# POE-3V3-boardschem.net
KiCad netlist of a schematic drawn in Altium Designer
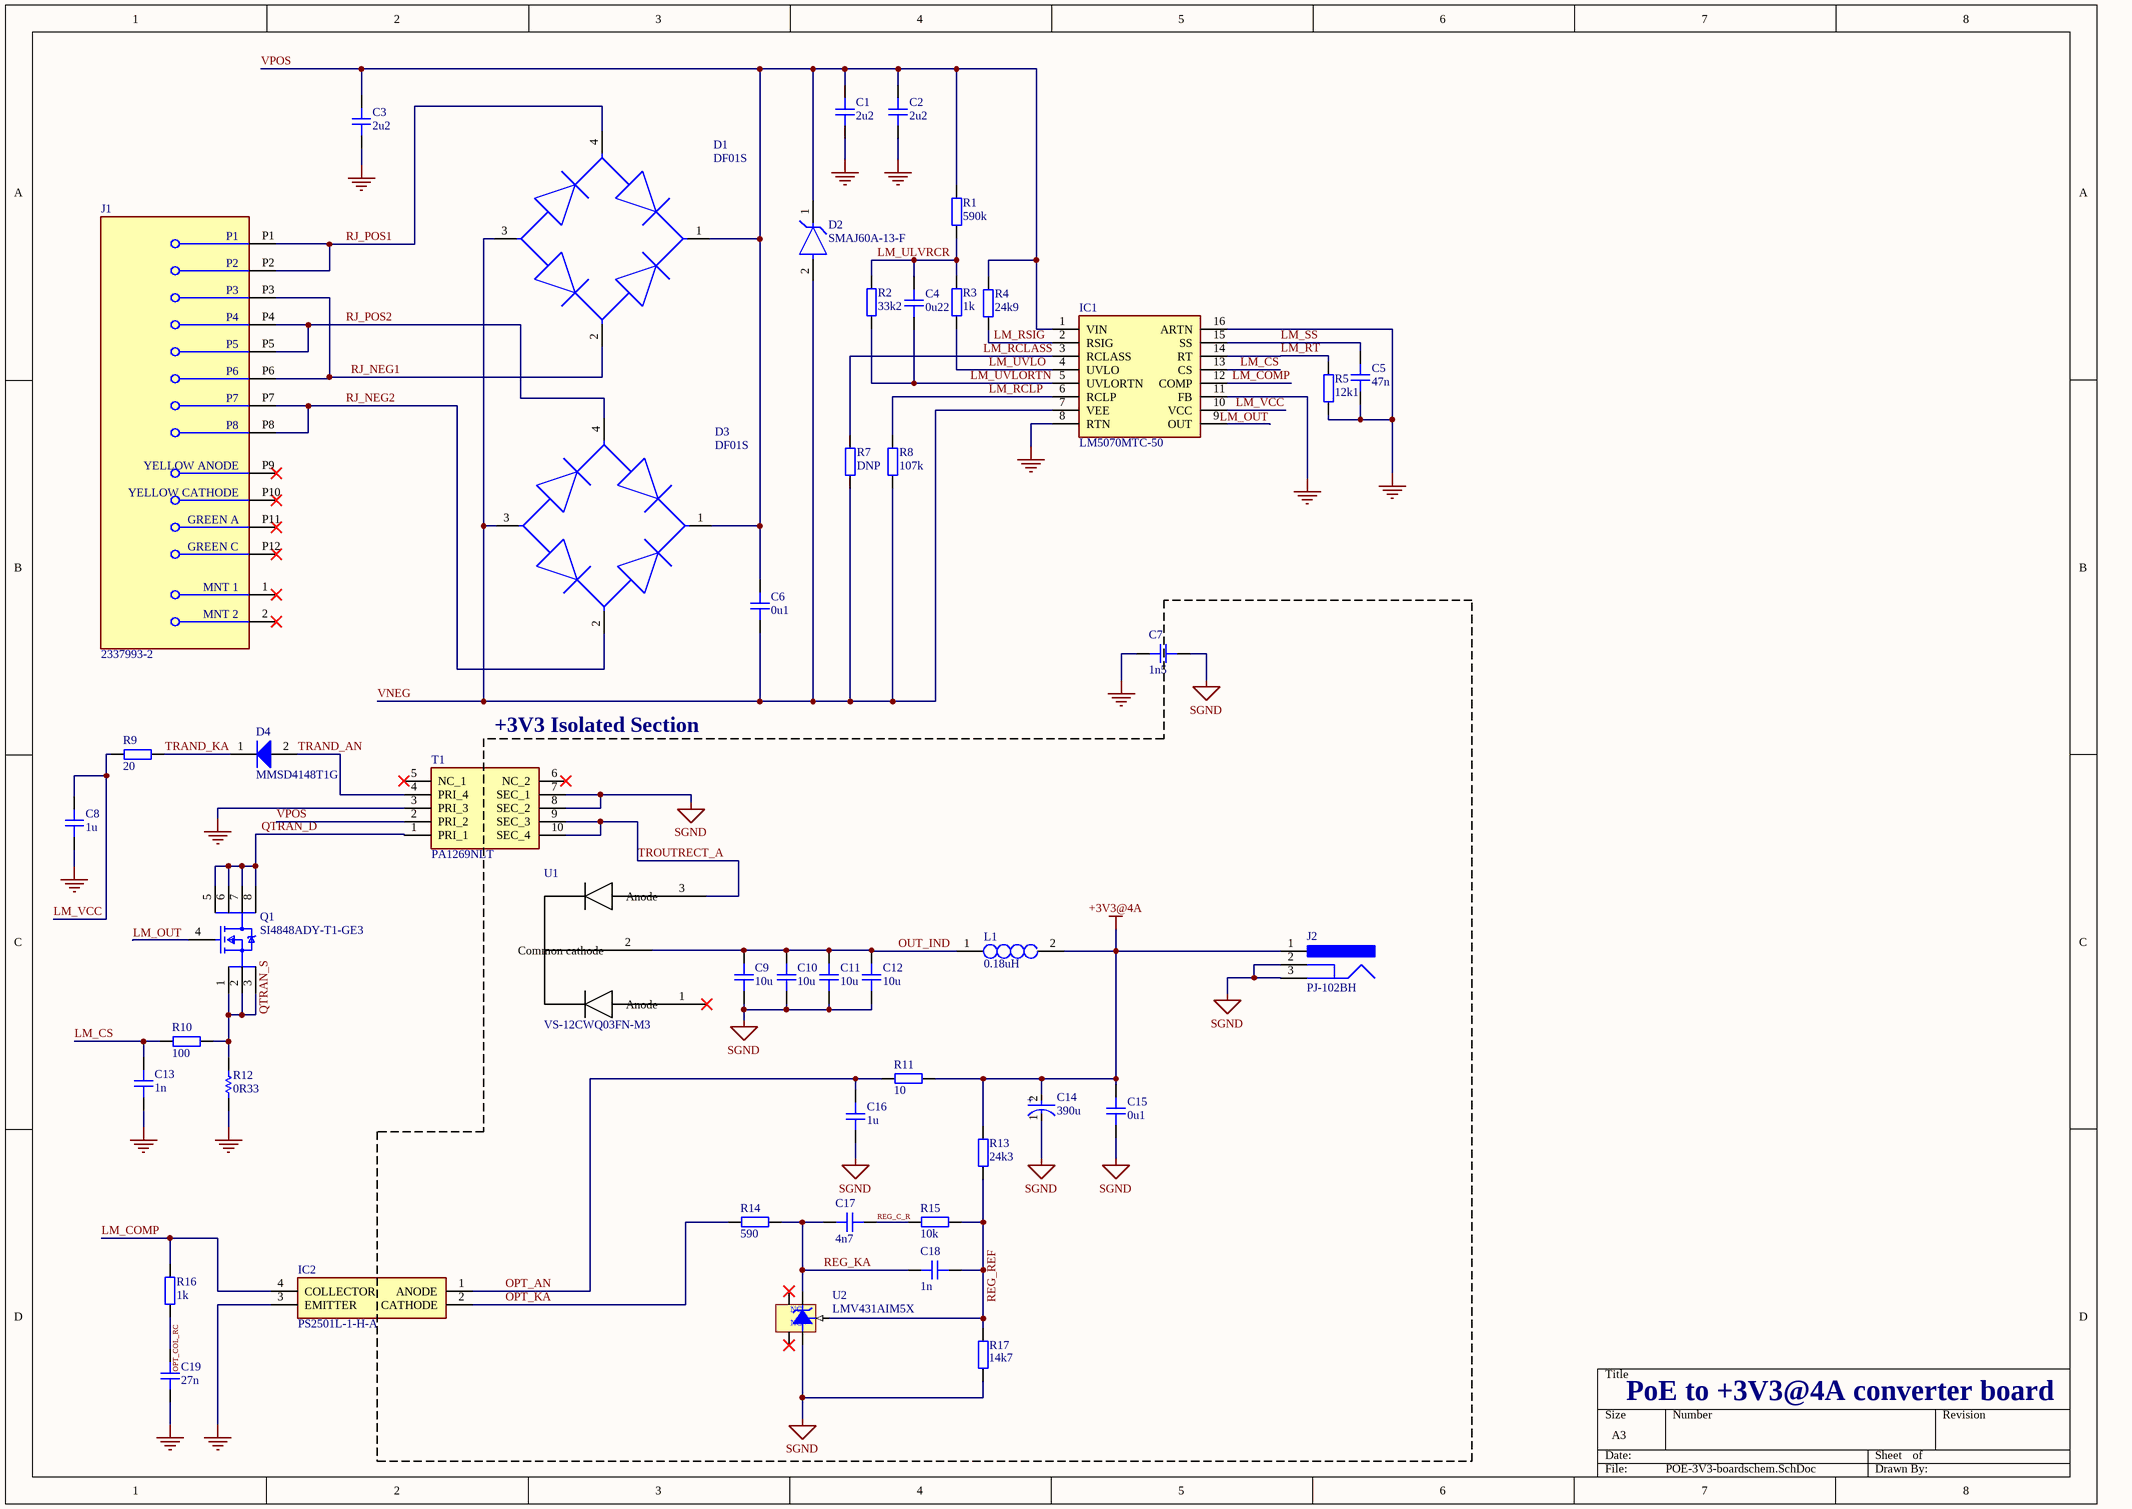
[diagram p0: POE-3V3-boardschem.SchDoc]

(export (version "E")
  (design (tool "Eeschema 10.0.6"))
  (components
    (comp (ref "C1")
      (value "2u2")
      (footprint "CAP_0805")
      (description "Capacitor SMD 0805")
      (libsource (lib "Schematic-Lib-PhilsLab") (part "CAP_0805"))
    )
    (comp (ref "C2")
      (value "2u2")
      (footprint "CAP_0805")
      (description "Capacitor SMD 0805")
      (libsource (lib "Schematic-Lib-PhilsLab") (part "CAP_0805"))
    )
    (comp (ref "C3")
      (value "2u2")
      (footprint "CAP_0805")
      (description "Capacitor SMD 0805")
      (libsource (lib "Schematic-Lib-PhilsLab") (part "CAP_0805"))
    )
    (comp (ref "C4")
      (value "0u22")
      (footprint "CAP_0805")
      (description "Capacitor SMD 0805")
      (libsource (lib "Schematic-Lib-PhilsLab") (part "CAP_0805"))
    )
    (comp (ref "C5")
      (value "47n")
      (footprint "CAP_0805")
      (description "Capacitor SMD 0805")
      (libsource (lib "Schematic-Lib-PhilsLab") (part "CAP_0805"))
    )
    (comp (ref "C6")
      (value "0u1")
      (footprint "CAP_0805")
      (description "Capacitor SMD 0805")
      (libsource (lib "Schematic-Lib-PhilsLab") (part "CAP_0805"))
    )
    (comp (ref "C7")
      (value "1n5")
      (footprint "CAP_0805")
      (description "Capacitor SMD 0805")
      (libsource (lib "Schematic-Lib-PhilsLab") (part "CAP_0805"))
    )
    (comp (ref "C8")
      (value "1u")
      (footprint "CAP_0805")
      (description "Capacitor SMD 0805")
      (libsource (lib "Schematic-Lib-PhilsLab") (part "CAP_0805"))
    )
    (comp (ref "C9")
      (value "10u")
      (footprint "CAP_1206")
      (description "Capacitor SMD 1206")
      (libsource (lib "Schematic-Lib-PhilsLab") (part "CAP_1206"))
    )
    (comp (ref "C10")
      (value "10u")
      (footprint "CAP_1206")
      (description "Capacitor SMD 1206")
      (libsource (lib "Schematic-Lib-PhilsLab") (part "CAP_1206"))
    )
    (comp (ref "C11")
      (value "10u")
      (footprint "CAP_1206")
      (description "Capacitor SMD 1206")
      (libsource (lib "Schematic-Lib-PhilsLab") (part "CAP_1206"))
    )
    (comp (ref "C12")
      (value "10u")
      (footprint "CAP_1206")
      (description "Capacitor SMD 1206")
      (libsource (lib "Schematic-Lib-PhilsLab") (part "CAP_1206"))
    )
    (comp (ref "C13")
      (value "1n")
      (footprint "CAP_0805")
      (description "Capacitor SMD 0805")
      (libsource (lib "Schematic-Lib-PhilsLab") (part "CAP_0805"))
    )
    (comp (ref "C14")
      (value "390u")
      (footprint "FP-RAD-TH-D_8_0_5-L_15_1-MFG")
      (description "Aluminum Electrolytic Capacitors (Radial Lead Type) 390uF ±20% 25V")
      (fields (field (name "TOLERANCE") "20%") (field (name "VOLTAGE") "25V"))
      (libsource (lib "Altium Content Vault") (part "a00bbbee19879c290e62620ae7e47b1"))
    )
    (comp (ref "C15")
      (value "0u1")
      (footprint "CAP_0805")
      (description "Capacitor SMD 0805")
      (libsource (lib "Schematic-Lib-PhilsLab") (part "CAP_0805"))
    )
    (comp (ref "C16")
      (value "1u")
      (footprint "CAP_1206")
      (description "Capacitor SMD 1206")
      (libsource (lib "Schematic-Lib-PhilsLab") (part "CAP_1206"))
    )
    (comp (ref "C17")
      (value "4n7")
      (footprint "CAP_1206")
      (description "Capacitor SMD 1206")
      (libsource (lib "Schematic-Lib-PhilsLab") (part "CAP_1206"))
    )
    (comp (ref "C18")
      (value "1n")
      (footprint "CAP_1206")
      (description "Capacitor SMD 1206")
      (libsource (lib "Schematic-Lib-PhilsLab") (part "CAP_1206"))
    )
    (comp (ref "C19")
      (value "27n")
      (footprint "CAP_1206")
      (description "Capacitor SMD 1206")
      (libsource (lib "Schematic-Lib-PhilsLab") (part "CAP_1206"))
    )
    (comp (ref "D1")
      (value "DF01S")
      (footprint "FP-DF-S-MFG")
      (description "BRIDGE RECT 1PHASE 100V 1A DFS")
      (libsource (lib "Altium Content Vault") (part "07528f16604ad27f2258f3ec450d36f"))
    )
    (comp (ref "D2")
      (value "SMAJ60A-13-F")
      (footprint "FP-SMA-MFG")
      (description "TVS DIODE 60V 96.8V SMA")
      (fields
        (field (name "MANUFACTURER") "Diodes Inc.")
        (field (name "OCTOPART") "https://octopart.com/smaj60a-13-f-diodes+inc.-350240")
      )
      (libsource (lib "Altium Content Vault") (part "f813f71cba58e380607f5dd3caf9714"))
    )
    (comp (ref "D3")
      (value "DF01S")
      (footprint "FP-DF-S-MFG")
      (description "BRIDGE RECT 1PHASE 100V 1A DFS")
      (libsource (lib "Altium Content Vault") (part "07528f16604ad27f2258f3ec450d36f"))
    )
    (comp (ref "D4")
      (value "MMSD4148T1G")
      (footprint "ONSC-SOD-123-2-425-04_V")
      (description "Switching Diode, 2-Pin SOD-123, Pb-Free, Tape and Reel")
      (fields (field (name "MANUFACTURER") "On Semiconductor"))
      (libsource (lib "Altium Content Vault") (part "ONSC-D-K1A2-2"))
    )
    (comp (ref "IC1")
      (value "LM5070MTC-50")
      (footprint "SamacSys:SOP65P640X120-16N")
      (description "Integrated Circuit")
      (fields (field (name "MOUSER PART NUMBER") "926-LM5070MTC-50"))
      (libsource (lib "*") (part "LM5070MTC-50"))
    )
    (comp (ref "IC2")
      (value "PS2501L-1-H-A")
      (footprint "SamacSys:SOP254P960X400-4N")
      (description "Integrated Circuit")
      (fields (field (name "MOUSER PART NUMBER") "968-PS2501L-1-H-A"))
      (libsource (lib "*") (part "PS2501L-1-H-A"))
    )
    (comp (ref "J1")
      (value "2337993-2")
      (footprint "FP-2337993-2-MFG")
      (description "RJ45 JACK MAG. POE 10/100 LED 1X")
      (fields
        (field (name "MANUFACTURER") "TE Connectivity")
        (field (name "OCTOPART") "https://octopart.com/2337993-2-te+connectivity-99778114")
      )
      (libsource (lib "Altium Content Vault") (part "b4e1c9a47ad5bbbc9e514b05e68767f"))
    )
    (comp (ref "J2")
      (value "PJ-102BH")
      (footprint "CUI-PJ-102BH_V")
      (fields (field (name "MANUFACTURER") "CUIInc."))
      (libsource (lib "Altium Content Vault") (part "JACK-2CD3-RN"))
    )
    (comp (ref "L1")
      (value "0.18uH")
      (footprint "SamacSys:DO1813H181MLD")
      (description "Inductor")
      (fields
        (field (name "MANUFACTURER_PART_NUMBER") "DO1813H-181MLD")
        (field (name "MOUSER PART NUMBER") "994-DO1813H-181MLD")
      )
      (libsource (lib "*") (part "DO1813H-181MLD"))
    )
    (comp (ref "Q1")
      (value "SI4848ADY-T1-GE3")
      (footprint "FP-C-06527-MFG")
      (description "MOSFET N-CH 150V 5.5A 8SOIC")
      (fields
        (field (name "MANUFACTURER") "Vishay")
        (field (name "OCTOPART") "https://octopart.com/si4848ady-t1-ge3-vishay-88182557")
      )
      (libsource (lib "Altium Content Vault") (part "7a16ee1d7ae3acce42eca13e4b0f561"))
    )
    (comp (ref "R1")
      (value "590k")
      (footprint "RES_0805")
      (description "Resistor SMD 0805")
      (libsource (lib "Schematic-Lib-PhilsLab") (part "RES_0805"))
    )
    (comp (ref "R2")
      (value "33k2")
      (footprint "RES_0805")
      (description "Resistor SMD 0805")
      (libsource (lib "Schematic-Lib-PhilsLab") (part "RES_0805"))
    )
    (comp (ref "R3")
      (value "1k")
      (footprint "RES_0805")
      (description "Resistor SMD 0805")
      (libsource (lib "Schematic-Lib-PhilsLab") (part "RES_0805"))
    )
    (comp (ref "R4")
      (value "24k9")
      (footprint "RES_0805")
      (description "Resistor SMD 0805")
      (libsource (lib "Schematic-Lib-PhilsLab") (part "RES_0805"))
    )
    (comp (ref "R5")
      (value "12k1")
      (footprint "RES_0805")
      (description "Resistor SMD 0805")
      (libsource (lib "Schematic-Lib-PhilsLab") (part "RES_0805"))
    )
    (comp (ref "R7")
      (value "DNP")
      (footprint "RES_0805")
      (description "Resistor SMD 0805")
      (libsource (lib "Schematic-Lib-PhilsLab") (part "RES_0805"))
    )
    (comp (ref "R8")
      (value "107k")
      (footprint "RES_0805")
      (description "Resistor SMD 0805")
      (libsource (lib "Schematic-Lib-PhilsLab") (part "RES_0805"))
    )
    (comp (ref "R9")
      (value "20")
      (footprint "RES_0805")
      (description "Resistor SMD 0805")
      (libsource (lib "Schematic-Lib-PhilsLab") (part "RES_0805"))
    )
    (comp (ref "R10")
      (value "100")
      (footprint "RES_0805")
      (description "Resistor SMD 0805")
      (libsource (lib "Schematic-Lib-PhilsLab") (part "RES_0805"))
    )
    (comp (ref "R11")
      (value "10")
      (footprint "RES_0805")
      (description "Resistor SMD 0805")
      (libsource (lib "Schematic-Lib-PhilsLab") (part "RES_0805"))
    )
    (comp (ref "R12")
      (value "0R33")
      (footprint "RESC3126X65X50NL10T20")
      (fields (field (name "PART NUMBER") "RL1210FR-070R33L") (field (name "MANUFACTURER") "Yageo"))
      (libsource (lib "Altium Content Vault") (part "RES"))
    )
    (comp (ref "R13")
      (value "24k3")
      (footprint "RES_0805")
      (description "Resistor SMD 0805")
      (libsource (lib "Schematic-Lib-PhilsLab") (part "RES_0805"))
    )
    (comp (ref "R14")
      (value "590")
      (footprint "RES_0805")
      (description "Resistor SMD 0805")
      (libsource (lib "Schematic-Lib-PhilsLab") (part "RES_0805"))
    )
    (comp (ref "R15")
      (value "10k")
      (footprint "RES_0805")
      (description "Resistor SMD 0805")
      (libsource (lib "Schematic-Lib-PhilsLab") (part "RES_0805"))
    )
    (comp (ref "R16")
      (value "1k")
      (footprint "RES_0805")
      (description "Resistor SMD 0805")
      (libsource (lib "Schematic-Lib-PhilsLab") (part "RES_0805"))
    )
    (comp (ref "R17")
      (value "14k7")
      (footprint "RES_0805")
      (description "Resistor SMD 0805")
      (libsource (lib "Schematic-Lib-PhilsLab") (part "RES_0805"))
    )
    (comp (ref "T1")
      (value "PA1269NLT")
      (footprint "SamacSys:PA1269NLT")
      (description "Transformer")
      (fields (field (name "MOUSER PART NUMBER") "673-PA1269NLT"))
      (libsource (lib "*") (part "PA1269NLT"))
    )
    (comp (ref "U1")
      (value "VS-12CWQ03FN-M3")
      (footprint "DPAK_03FN-M3_VIS")
      (description "Schottky - D-PAK")
      (fields (field (name "COPYRIGHT") "Copyright (C) 2025 Ultra Librarian. All rights reserved."))
      (libsource (lib "VS-12CWQ03FN-M3") (part "VS-12CWQ03FN-M3"))
    )
    (comp (ref "U2")
      (value "LMV431AIM5X")
      (footprint "DBV0005A_M")
      (description "Low-Voltage (1.24V) Adjustable Precision Shunt Regulators, 5-pin SOT-23")
      (fields (field (name "MANUFACTURER") "Texas Instruments"))
      (libsource (lib "Altium Content Vault") (part "PM-REG-LMV431-5"))
    )
  )
  (nets
    (net (code "1") (name "+3V3@4A") (class "Default")
      (node (ref "C14") (pin "2") (pinfunction "A_2") (pintype "passive"))
      (node (ref "C15") (pin "2") (pinfunction "2_2") (pintype "passive"))
      (node (ref "J2") (pin "1") (pinfunction "1_1") (pintype "passive"))
      (node (ref "L1") (pin "2") (pinfunction "2_2") (pintype "passive"))
      (node (ref "R11") (pin "2") (pinfunction "2_2") (pintype "passive"))
      (node (ref "R13") (pin "1") (pinfunction "1_1") (pintype "passive"))
    )
    (net (code "2") (name "/LM_COMP") (class "Default")
      (node (ref "IC1") (pin "12") (pinfunction "COMP_12") (pintype "passive"))
      (node (ref "IC2") (pin "4") (pinfunction "COLLECTOR_4") (pintype "passive"))
      (node (ref "R16") (pin "1") (pinfunction "1_1") (pintype "passive"))
    )
    (net (code "3") (name "/LM_CS") (class "Default")
      (node (ref "C13") (pin "2") (pinfunction "2_2") (pintype "passive"))
      (node (ref "IC1") (pin "13") (pinfunction "CS_13") (pintype "passive"))
      (node (ref "R10") (pin "2") (pinfunction "2_2") (pintype "passive"))
    )
    (net (code "4") (name "/LM_OUT") (class "Default")
      (node (ref "IC1") (pin "9") (pinfunction "OUT_9") (pintype "passive"))
      (node (ref "Q1") (pin "4") (pinfunction "G_4") (pintype "passive"))
    )
    (net (code "5") (name "/LM_RCLASS") (class "Default")
      (node (ref "IC1") (pin "3") (pinfunction "RCLASS_3") (pintype "passive"))
      (node (ref "R7") (pin "2") (pinfunction "2_2") (pintype "passive"))
    )
    (net (code "6") (name "/LM_RCLP") (class "Default")
      (node (ref "IC1") (pin "6") (pinfunction "RCLP_6") (pintype "passive"))
      (node (ref "R8") (pin "2") (pinfunction "2_2") (pintype "passive"))
    )
    (net (code "7") (name "/LM_RSIG") (class "Default")
      (node (ref "IC1") (pin "2") (pinfunction "RSIG_2") (pintype "passive"))
      (node (ref "R4") (pin "1") (pinfunction "1_1") (pintype "passive"))
    )
    (net (code "8") (name "/LM_RT") (class "Default")
      (node (ref "IC1") (pin "14") (pinfunction "RT_14") (pintype "passive"))
      (node (ref "R5") (pin "2") (pinfunction "2_2") (pintype "passive"))
    )
    (net (code "9") (name "/LM_SS") (class "Default")
      (node (ref "C5") (pin "2") (pinfunction "2_2") (pintype "passive"))
      (node (ref "IC1") (pin "15") (pinfunction "SS_15") (pintype "passive"))
    )
    (net (code "10") (name "/LM_ULVRCR") (class "Default")
      (node (ref "C4") (pin "2") (pinfunction "2_2") (pintype "passive"))
      (node (ref "R1") (pin "1") (pinfunction "1_1") (pintype "passive"))
      (node (ref "R2") (pin "2") (pinfunction "2_2") (pintype "passive"))
      (node (ref "R3") (pin "2") (pinfunction "2_2") (pintype "passive"))
    )
    (net (code "11") (name "/LM_UVLO") (class "Default")
      (node (ref "IC1") (pin "4") (pinfunction "UVLO_4") (pintype "passive"))
      (node (ref "R3") (pin "1") (pinfunction "1_1") (pintype "passive"))
    )
    (net (code "12") (name "/LM_UVLORTN") (class "Default")
      (node (ref "C4") (pin "1") (pinfunction "1_1") (pintype "passive"))
      (node (ref "IC1") (pin "5") (pinfunction "UVLORTN_5") (pintype "passive"))
      (node (ref "R2") (pin "1") (pinfunction "1_1") (pintype "passive"))
    )
    (net (code "13") (name "/LM_VCC") (class "Default")
      (node (ref "C8") (pin "2") (pinfunction "2_2") (pintype "passive"))
      (node (ref "IC1") (pin "10") (pinfunction "VCC_10") (pintype "passive"))
      (node (ref "R9") (pin "2") (pinfunction "2_2") (pintype "passive"))
    )
    (net (code "14") (name "/OPT_AN") (class "Default")
      (node (ref "C16") (pin "2") (pinfunction "2_2") (pintype "passive"))
      (node (ref "IC2") (pin "1") (pinfunction "ANODE_1") (pintype "passive"))
      (node (ref "R11") (pin "1") (pinfunction "1_1") (pintype "passive"))
    )
    (net (code "15") (name "/OPT_COL_RC") (class "Default")
      (node (ref "C19") (pin "1") (pinfunction "1_1") (pintype "passive"))
      (node (ref "R16") (pin "2") (pinfunction "2_2") (pintype "passive"))
    )
    (net (code "16") (name "/OPT_KA") (class "Default")
      (node (ref "IC2") (pin "2") (pinfunction "CATHODE_2") (pintype "passive"))
      (node (ref "R14") (pin "1") (pinfunction "1_1") (pintype "passive"))
    )
    (net (code "17") (name "/OUT_IND") (class "Default")
      (node (ref "C10") (pin "2") (pinfunction "2_2") (pintype "passive"))
      (node (ref "C11") (pin "2") (pinfunction "2_2") (pintype "passive"))
      (node (ref "C12") (pin "2") (pinfunction "2_2") (pintype "passive"))
      (node (ref "C9") (pin "2") (pinfunction "2_2") (pintype "passive"))
      (node (ref "L1") (pin "1") (pinfunction "1_1") (pintype "passive"))
      (node (ref "U1") (pin "2") (pinfunction "Common_cathode_2") (pintype "passive"))
    )
    (net (code "18") (name "/QTRAN_D") (class "Default")
      (node (ref "Q1") (pin "5") (pinfunction "D_5") (pintype "passive"))
      (node (ref "Q1") (pin "6") (pinfunction "D_6") (pintype "passive"))
      (node (ref "Q1") (pin "7") (pinfunction "D_7") (pintype "passive"))
      (node (ref "Q1") (pin "8") (pinfunction "D_8") (pintype "passive"))
      (node (ref "T1") (pin "1") (pinfunction "PRI_1_1") (pintype "passive"))
    )
    (net (code "19") (name "/QTRAN_S") (class "Default")
      (node (ref "Q1") (pin "1") (pinfunction "S_1") (pintype "passive"))
      (node (ref "Q1") (pin "2") (pinfunction "S_2") (pintype "passive"))
      (node (ref "Q1") (pin "3") (pinfunction "S_3") (pintype "passive"))
      (node (ref "R10") (pin "1") (pinfunction "1_1") (pintype "passive"))
      (node (ref "R12") (pin "2") (pinfunction "2_2") (pintype "passive"))
    )
    (net (code "20") (name "/REG_C_R") (class "Default")
      (node (ref "C17") (pin "1") (pinfunction "1_1") (pintype "passive"))
      (node (ref "R15") (pin "1") (pinfunction "1_1") (pintype "passive"))
    )
    (net (code "21") (name "/REG_KA") (class "Default")
      (node (ref "C17") (pin "2") (pinfunction "2_2") (pintype "passive"))
      (node (ref "C18") (pin "2") (pinfunction "2_2") (pintype "passive"))
      (node (ref "R14") (pin "2") (pinfunction "2_2") (pintype "passive"))
      (node (ref "U2") (pin "3") (pinfunction "K_3") (pintype "passive"))
    )
    (net (code "22") (name "/REG_REF") (class "Default")
      (node (ref "C18") (pin "1") (pinfunction "1_1") (pintype "passive"))
      (node (ref "R13") (pin "2") (pinfunction "2_2") (pintype "passive"))
      (node (ref "R15") (pin "2") (pinfunction "2_2") (pintype "passive"))
      (node (ref "R17") (pin "1") (pinfunction "1_1") (pintype "passive"))
      (node (ref "U2") (pin "4") (pinfunction "REF_4") (pintype "input"))
    )
    (net (code "23") (name "/RJ_NEG1") (class "Default")
      (node (ref "D1") (pin "2") (pinfunction "1_~_2") (pintype "passive"))
      (node (ref "J1") (pin "P3") (pinfunction "P3_P3") (pintype "passive"))
      (node (ref "J1") (pin "P6") (pinfunction "P6_P6") (pintype "passive"))
    )
    (net (code "24") (name "/RJ_NEG2") (class "Default")
      (node (ref "D3") (pin "2") (pinfunction "1_~_2") (pintype "passive"))
      (node (ref "J1") (pin "P7") (pinfunction "P7_P7") (pintype "passive"))
      (node (ref "J1") (pin "P8") (pinfunction "P8_P8") (pintype "passive"))
    )
    (net (code "25") (name "/RJ_POS1") (class "Default")
      (node (ref "D1") (pin "4") (pinfunction "2_~_4") (pintype "passive"))
      (node (ref "J1") (pin "P1") (pinfunction "P1_P1") (pintype "passive"))
      (node (ref "J1") (pin "P2") (pinfunction "P2_P2") (pintype "passive"))
    )
    (net (code "26") (name "/RJ_POS2") (class "Default")
      (node (ref "D3") (pin "4") (pinfunction "2_~_4") (pintype "passive"))
      (node (ref "J1") (pin "P4") (pinfunction "P4_P4") (pintype "passive"))
      (node (ref "J1") (pin "P5") (pinfunction "P5_P5") (pintype "passive"))
    )
    (net (code "27") (name "/TRAND_AN") (class "Default")
      (node (ref "D4") (pin "2") (pinfunction "A_2") (pintype "passive"))
      (node (ref "T1") (pin "4") (pinfunction "PRI_4_4") (pintype "passive"))
    )
    (net (code "28") (name "/TRAND_KA") (class "Default")
      (node (ref "D4") (pin "1") (pinfunction "K_1") (pintype "passive"))
      (node (ref "R9") (pin "1") (pinfunction "1_1") (pintype "passive"))
    )
    (net (code "29") (name "/TROUTRECT_A") (class "Default")
      (node (ref "T1") (pin "10") (pinfunction "SEC_4_10") (pintype "passive"))
      (node (ref "T1") (pin "9") (pinfunction "SEC_3_9") (pintype "passive"))
      (node (ref "U1") (pin "3") (pinfunction "Anode_3") (pintype "passive"))
    )
    (net (code "30") (name "/VNEG") (class "Default")
      (node (ref "C6") (pin "1") (pinfunction "1_1") (pintype "passive"))
      (node (ref "D1") (pin "3") (pinfunction "-_3") (pintype "passive"))
      (node (ref "D2") (pin "2") (pinfunction "A_2") (pintype "passive"))
      (node (ref "D3") (pin "3") (pinfunction "-_3") (pintype "passive"))
      (node (ref "IC1") (pin "7") (pinfunction "VEE_7") (pintype "passive"))
      (node (ref "R7") (pin "1") (pinfunction "1_1") (pintype "passive"))
      (node (ref "R8") (pin "1") (pinfunction "1_1") (pintype "passive"))
    )
    (net (code "31") (name "/VPOS") (class "Default")
      (node (ref "C1") (pin "2") (pinfunction "2_2") (pintype "passive"))
      (node (ref "C2") (pin "2") (pinfunction "2_2") (pintype "passive"))
      (node (ref "C3") (pin "2") (pinfunction "2_2") (pintype "passive"))
      (node (ref "C6") (pin "2") (pinfunction "2_2") (pintype "passive"))
      (node (ref "D1") (pin "1") (pinfunction "+_1") (pintype "passive"))
      (node (ref "D2") (pin "1") (pinfunction "C_1") (pintype "passive"))
      (node (ref "D3") (pin "1") (pinfunction "+_1") (pintype "passive"))
      (node (ref "IC1") (pin "1") (pinfunction "VIN_1") (pintype "passive"))
      (node (ref "R1") (pin "2") (pinfunction "2_2") (pintype "passive"))
      (node (ref "R4") (pin "2") (pinfunction "2_2") (pintype "passive"))
      (node (ref "T1") (pin "2") (pinfunction "PRI_2_2") (pintype "passive"))
    )
    (net (code "32") (name "GND") (class "Default")
      (node (ref "C1") (pin "1") (pinfunction "1_1") (pintype "passive"))
      (node (ref "C13") (pin "1") (pinfunction "1_1") (pintype "passive"))
      (node (ref "C19") (pin "2") (pinfunction "2_2") (pintype "passive"))
      (node (ref "C2") (pin "1") (pinfunction "1_1") (pintype "passive"))
      (node (ref "C3") (pin "1") (pinfunction "1_1") (pintype "passive"))
      (node (ref "C5") (pin "1") (pinfunction "1_1") (pintype "passive"))
      (node (ref "C7") (pin "2") (pinfunction "2_2") (pintype "passive"))
      (node (ref "C8") (pin "1") (pinfunction "1_1") (pintype "passive"))
      (node (ref "IC1") (pin "11") (pinfunction "FB_11") (pintype "passive"))
      (node (ref "IC1") (pin "16") (pinfunction "ARTN_16") (pintype "passive"))
      (node (ref "IC1") (pin "8") (pinfunction "RTN_8") (pintype "passive"))
      (node (ref "IC2") (pin "3") (pinfunction "EMITTER_3") (pintype "passive"))
      (node (ref "R12") (pin "1") (pinfunction "1_1") (pintype "passive"))
      (node (ref "R5") (pin "1") (pinfunction "1_1") (pintype "passive"))
      (node (ref "T1") (pin "3") (pinfunction "PRI_3_3") (pintype "passive"))
    )
    (net (code "33") (name "SGND") (class "Default")
      (node (ref "C10") (pin "1") (pinfunction "1_1") (pintype "passive"))
      (node (ref "C11") (pin "1") (pinfunction "1_1") (pintype "passive"))
      (node (ref "C12") (pin "1") (pinfunction "1_1") (pintype "passive"))
      (node (ref "C14") (pin "1") (pinfunction "C_1") (pintype "passive"))
      (node (ref "C15") (pin "1") (pinfunction "1_1") (pintype "passive"))
      (node (ref "C16") (pin "1") (pinfunction "1_1") (pintype "passive"))
      (node (ref "C7") (pin "1") (pinfunction "1_1") (pintype "passive"))
      (node (ref "C9") (pin "1") (pinfunction "1_1") (pintype "passive"))
      (node (ref "J2") (pin "2") (pinfunction "2_2") (pintype "passive"))
      (node (ref "J2") (pin "3") (pinfunction "3_3") (pintype "passive"))
      (node (ref "R17") (pin "2") (pinfunction "2_2") (pintype "passive"))
      (node (ref "T1") (pin "7") (pinfunction "SEC_1_7") (pintype "passive"))
      (node (ref "T1") (pin "8") (pinfunction "SEC_2_8") (pintype "passive"))
      (node (ref "U2") (pin "5") (pinfunction "A_5") (pintype "passive"))
    )
    (net (code "34") (name "unconnected-(J1-GREEN_A-PadP11)") (class "Default")
      (node (ref "J1") (pin "P11") (pinfunction "GREEN_A_P11") (pintype "passive+no_connect"))
    )
    (net (code "35") (name "unconnected-(J1-GREEN_C-PadP12)") (class "Default")
      (node (ref "J1") (pin "P12") (pinfunction "GREEN_C_P12") (pintype "passive+no_connect"))
    )
    (net (code "36") (name "unconnected-(J1-MNT_1-Pad1)") (class "Default")
      (node (ref "J1") (pin "1") (pinfunction "MNT_1_1") (pintype "passive+no_connect"))
    )
    (net (code "37") (name "unconnected-(J1-MNT_2-Pad2)") (class "Default")
      (node (ref "J1") (pin "2") (pinfunction "MNT_2_2") (pintype "passive+no_connect"))
    )
    (net (code "38") (name "unconnected-(J1-YELLOW_ANODE-PadP9)") (class "Default")
      (node (ref "J1") (pin "P9") (pinfunction "YELLOW_ANODE_P9") (pintype "passive+no_connect"))
    )
    (net (code "39") (name "unconnected-(J1-YELLOW_CATHODE-PadP10)") (class "Default")
      (node (ref "J1") (pin "P10") (pinfunction "YELLOW_CATHODE_P10") (pintype "passive+no_connect"))
    )
    (net (code "40") (name "unconnected-(T1-NC_1-Pad5)") (class "Default")
      (node (ref "T1") (pin "5") (pinfunction "NC_1_5") (pintype "passive+no_connect"))
    )
    (net (code "41") (name "unconnected-(T1-NC_2-Pad6)") (class "Default")
      (node (ref "T1") (pin "6") (pinfunction "NC_2_6") (pintype "passive+no_connect"))
    )
    (net (code "42") (name "unconnected-(U1-Anode-Pad1)") (class "Default")
      (node (ref "U1") (pin "1") (pinfunction "Anode_1") (pintype "passive+no_connect"))
    )
    (net (code "43") (name "unconnected-(U2-NC-Pad1)") (class "Default")
      (node (ref "U2") (pin "1") (pinfunction "NC_1") (pintype "passive+no_connect"))
    )
    (net (code "44") (name "unconnected-(U2-NC-Pad2)") (class "Default")
      (node (ref "U2") (pin "2") (pinfunction "NC_2") (pintype "passive+no_connect"))
    )
  )
)
